# h_bridge.net
KiCad netlist of a schematic drawn in Altium Designer
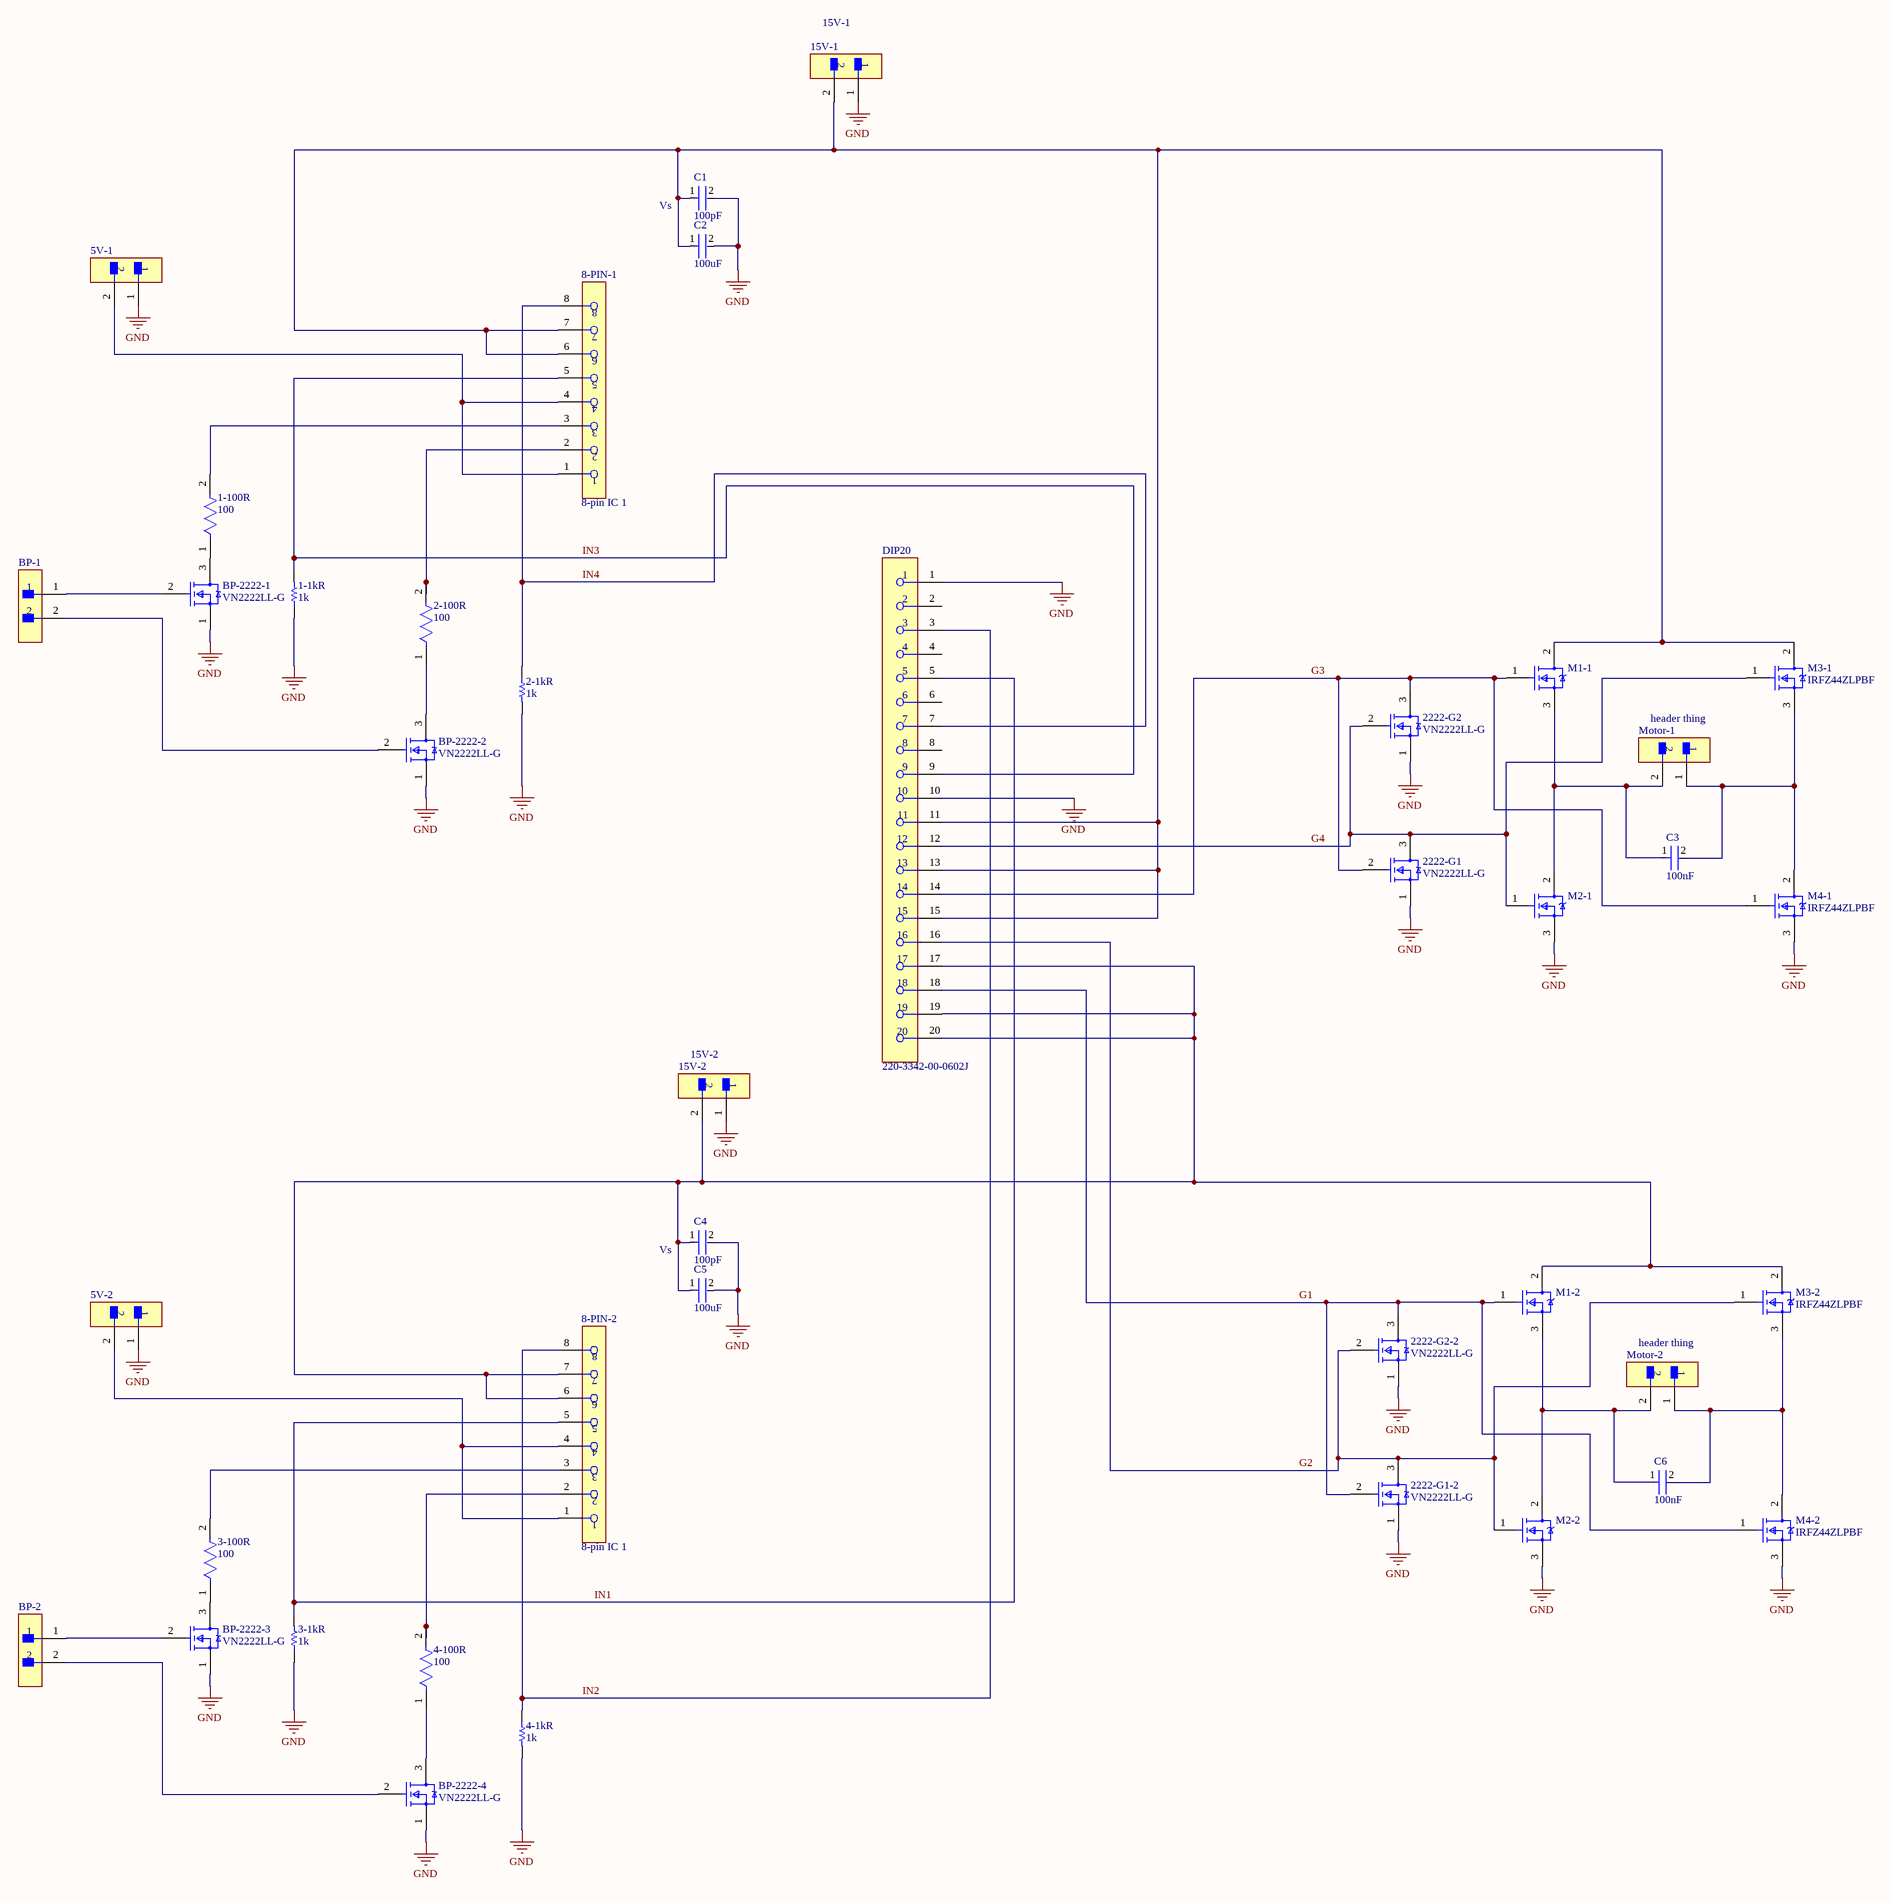
[diagram p0: h bridge.SchDoc]

(export (version "E")
  (design (tool "Eeschema 10.0.6"))
  (components
    (comp (ref "1-1kR")
      (value "1k")
      (footprint "RESC3116X65X40ML10T20")
      (description "Chip Resistor, 1 KOhm, +/- 1%, 0.25 W, -55 to 155 degC, 1206 (3216 Metric), RoHS, Tape and Reel")
      (fields (field (name "TOLERANCE") "1%") (field (name "MANUFACTURER") "Yageo"))
      (libsource (lib "Altium Content Vault") (part "RES-2"))
    )
    (comp (ref "1-100R")
      (value "100")
      (footprint "FP-CRCW1206-e3-MFG")
      (description "RES Thick Film, 100Ω, 1%, 0.25W, 100ppm/°C, 1206")
      (fields (field (name "TOLERANCE") "1%"))
      (libsource (lib "Altium Content Vault") (part "1029c3af85768c4190bb7ad29bc67b5"))
    )
    (comp (ref "2-1kR")
      (value "1k")
      (footprint "RESC3116X65X40ML10T20")
      (description "Chip Resistor, 1 KOhm, +/- 1%, 0.25 W, -55 to 155 degC, 1206 (3216 Metric), RoHS, Tape and Reel")
      (fields (field (name "TOLERANCE") "1%") (field (name "MANUFACTURER") "Yageo"))
      (libsource (lib "Altium Content Vault") (part "RES-2"))
    )
    (comp (ref "2-100R")
      (value "100")
      (footprint "FP-CRCW1206-e3-MFG")
      (description "RES Thick Film, 100Ω, 1%, 0.25W, 100ppm/°C, 1206")
      (fields (field (name "TOLERANCE") "1%"))
      (libsource (lib "Altium Content Vault") (part "1029c3af85768c4190bb7ad29bc67b5"))
    )
    (comp (ref "3-1kR")
      (value "1k")
      (footprint "RESC3116X65X40ML10T20")
      (description "Chip Resistor, 1 KOhm, +/- 1%, 0.25 W, -55 to 155 degC, 1206 (3216 Metric), RoHS, Tape and Reel")
      (fields (field (name "TOLERANCE") "1%") (field (name "MANUFACTURER") "Yageo"))
      (libsource (lib "Altium Content Vault") (part "RES-2"))
    )
    (comp (ref "3-100R")
      (value "100")
      (footprint "FP-CRCW1206-e3-MFG")
      (description "RES Thick Film, 100Ω, 1%, 0.25W, 100ppm/°C, 1206")
      (fields (field (name "TOLERANCE") "1%"))
      (libsource (lib "Altium Content Vault") (part "1029c3af85768c4190bb7ad29bc67b5"))
    )
    (comp (ref "4-1kR")
      (value "1k")
      (footprint "RESC3116X65X40ML10T20")
      (description "Chip Resistor, 1 KOhm, +/- 1%, 0.25 W, -55 to 155 degC, 1206 (3216 Metric), RoHS, Tape and Reel")
      (fields (field (name "TOLERANCE") "1%") (field (name "MANUFACTURER") "Yageo"))
      (libsource (lib "Altium Content Vault") (part "RES-2"))
    )
    (comp (ref "4-100R")
      (value "100")
      (footprint "FP-CRCW1206-e3-MFG")
      (description "RES Thick Film, 100Ω, 1%, 0.25W, 100ppm/°C, 1206")
      (fields (field (name "TOLERANCE") "1%"))
      (libsource (lib "Altium Content Vault") (part "1029c3af85768c4190bb7ad29bc67b5"))
    )
    (comp (ref "5V-1")
      (value "~")
      (footprint "FP-B2B-EH-A_LF_SN-MFG")
      (description "CONN HEADER VERT 2POS 2.5MM")
      (libsource (lib "") (part "3bc925449376181038e59eaffc5286c_1"))
    )
    (comp (ref "5V-2")
      (value "~")
      (footprint "FP-B2B-EH-A_LF_SN-MFG")
      (description "CONN HEADER VERT 2POS 2.5MM")
      (libsource (lib "") (part "3bc925449376181038e59eaffc5286c_1"))
    )
    (comp (ref "8-PIN-1")
      (value "8-pin IC 1")
      (footprint "FP-1-2199298-2-MFG")
      (description "CONN IC DIP SOCKET 8POS TIN")
      (libsource (lib "Altium Content Vault") (part "b0a0b555dd3abf3683e7c330df25cc4"))
    )
    (comp (ref "8-PIN-2")
      (value "8-pin IC 1")
      (footprint "FP-1-2199298-2-MFG")
      (description "CONN IC DIP SOCKET 8POS TIN")
      (libsource (lib "Altium Content Vault") (part "b0a0b555dd3abf3683e7c330df25cc4"))
    )
    (comp (ref "15V-1")
      (value "15V-1")
      (footprint "FP-B2B-EH-A_LF_SN-MFG")
      (description "CONN HEADER VERT 2POS 2.5MM")
      (libsource (lib "") (part "3bc925449376181038e59eaffc5286c_1"))
    )
    (comp (ref "15V-2")
      (value "15V-2")
      (footprint "FP-B2B-EH-A_LF_SN-MFG")
      (description "CONN HEADER VERT 2POS 2.5MM")
      (libsource (lib "") (part "3bc925449376181038e59eaffc5286c_1"))
    )
    (comp (ref "2222-G1")
      (value "VN2222LL-G")
      (footprint "FP-VN2222LL-G-MFG")
      (description "MOSFET N-CH 60V 0.23A TO92-3")
      (libsource (lib "Altium Content Vault") (part "4ab27c3d3892bfd5e8942bbbfba2a96"))
    )
    (comp (ref "2222-G1-2")
      (value "VN2222LL-G")
      (footprint "FP-VN2222LL-G-MFG")
      (description "MOSFET N-CH 60V 0.23A TO92-3")
      (libsource (lib "Altium Content Vault") (part "4ab27c3d3892bfd5e8942bbbfba2a96"))
    )
    (comp (ref "2222-G2")
      (value "VN2222LL-G")
      (footprint "FP-VN2222LL-G-MFG")
      (description "MOSFET N-CH 60V 0.23A TO92-3")
      (libsource (lib "Altium Content Vault") (part "4ab27c3d3892bfd5e8942bbbfba2a96"))
    )
    (comp (ref "2222-G2-2")
      (value "VN2222LL-G")
      (footprint "FP-VN2222LL-G-MFG")
      (description "MOSFET N-CH 60V 0.23A TO92-3")
      (libsource (lib "Altium Content Vault") (part "4ab27c3d3892bfd5e8942bbbfba2a96"))
    )
    (comp (ref "BP-1")
      (value "~")
      (footprint "FP-B2B-EH-A_LF_SN-MFG")
      (description "CONN HEADER VERT 2POS 2.5MM")
      (libsource (lib "Altium Content Vault") (part "3bc925449376181038e59eaffc5286c"))
    )
    (comp (ref "BP-2")
      (value "~")
      (footprint "FP-B2B-EH-A_LF_SN-MFG")
      (description "CONN HEADER VERT 2POS 2.5MM")
      (libsource (lib "Altium Content Vault") (part "3bc925449376181038e59eaffc5286c"))
    )
    (comp (ref "BP-2222-1")
      (value "VN2222LL-G")
      (footprint "FP-VN2222LL-G-MFG")
      (description "MOSFET N-CH 60V 0.23A TO92-3")
      (libsource (lib "Altium Content Vault") (part "4ab27c3d3892bfd5e8942bbbfba2a96"))
    )
    (comp (ref "BP-2222-2")
      (value "VN2222LL-G")
      (footprint "FP-VN2222LL-G-MFG")
      (description "MOSFET N-CH 60V 0.23A TO92-3")
      (libsource (lib "Altium Content Vault") (part "4ab27c3d3892bfd5e8942bbbfba2a96"))
    )
    (comp (ref "BP-2222-3")
      (value "VN2222LL-G")
      (footprint "FP-VN2222LL-G-MFG")
      (description "MOSFET N-CH 60V 0.23A TO92-3")
      (libsource (lib "Altium Content Vault") (part "4ab27c3d3892bfd5e8942bbbfba2a96"))
    )
    (comp (ref "BP-2222-4")
      (value "VN2222LL-G")
      (footprint "FP-VN2222LL-G-MFG")
      (description "MOSFET N-CH 60V 0.23A TO92-3")
      (libsource (lib "Altium Content Vault") (part "4ab27c3d3892bfd5e8942bbbfba2a96"))
    )
    (comp (ref "C1")
      (value "100pF")
      (footprint "FP-1206-L_3_2_0_2-W_1_6_0-MFG")
      (description "General Purpose Ceramic Capacitor, 1206, 100pF, 5%, NP0, 30ppm/°C, 100V")
      (fields (field (name "VOLTAGE") "63V") (field (name "TOLERANCE") "5%"))
      (libsource (lib "Altium Content Vault") (part "02cd4be3c70576c341d710602a673aa"))
    )
    (comp (ref "C2")
      (value "100uF")
      (footprint "FP-C3216-160-0_3-IPC_C")
      (description "Multilayer Ceramic Capacitors 100uF ±20% 10V X5R SMD 1206")
      (fields (field (name "VOLTAGE") "10V") (field (name "TOLERANCE") "20%"))
      (libsource (lib "Altium Content Vault") (part "02cd4be3c70576c341d710602a673aa"))
    )
    (comp (ref "C3")
      (value "100nF")
      (footprint "FP-1206-L_3_2_0_2-W_1_6_0-IPC_C")
      (description "General Purpose Ceramic Capacitor, 1206, 100nF, 5%, X7R, 15%, 100V")
      (fields (field (name "TOLERANCE") "5%") (field (name "VOLTAGE") "100V"))
      (libsource (lib "Altium Content Vault") (part "b4654b650e69147ec39a6b967a45e02"))
    )
    (comp (ref "C4")
      (value "100pF")
      (footprint "FP-1206-L_3_2_0_2-W_1_6_0-MFG")
      (description "General Purpose Ceramic Capacitor, 1206, 100pF, 5%, NP0, 30ppm/°C, 100V")
      (fields (field (name "VOLTAGE") "63V") (field (name "TOLERANCE") "5%"))
      (libsource (lib "Altium Content Vault") (part "02cd4be3c70576c341d710602a673aa"))
    )
    (comp (ref "C5")
      (value "100uF")
      (footprint "FP-C3216-160-0_3-IPC_C")
      (description "Multilayer Ceramic Capacitors 100uF ±20% 10V X5R SMD 1206")
      (fields (field (name "VOLTAGE") "10V") (field (name "TOLERANCE") "20%"))
      (libsource (lib "Altium Content Vault") (part "02cd4be3c70576c341d710602a673aa"))
    )
    (comp (ref "C6")
      (value "100nF")
      (footprint "FP-1206-L_3_2_0_2-W_1_6_0-IPC_C")
      (description "General Purpose Ceramic Capacitor, 1206, 100nF, 5%, X7R, 15%, 100V")
      (fields (field (name "TOLERANCE") "5%") (field (name "VOLTAGE") "100V"))
      (libsource (lib "Altium Content Vault") (part "b4654b650e69147ec39a6b967a45e02"))
    )
    (comp (ref "DIP20")
      (value "220-3342-00-0602J")
      (footprint "FP-220-3342-00-0602J-0")
      (description "20 (2 x 10) Pos DIP, ZIF (ZIP), 0.3\" (7.62mm) Row Spacing Socket Gold Connector")
      (fields (field (name "MANUFACTURER") "3M"))
      (libsource (lib "Altium Content Vault") (part "dba14e038e6f7492952b7f1e871f183"))
    )
    (comp (ref "M1-1")
      (value "IRFZ44ZLPBF")
      (footprint "FP-PG-TO262-3-MFG")
      (description "MOSFET N-CH 55V 51A TO262")
      (libsource (lib "Altium Content Vault") (part "b09f7f152735e370c1ea22a33fa83d6"))
    )
    (comp (ref "M1-2")
      (value "IRFZ44ZLPBF")
      (footprint "FP-PG-TO262-3-MFG")
      (description "MOSFET N-CH 55V 51A TO262")
      (libsource (lib "Altium Content Vault") (part "b09f7f152735e370c1ea22a33fa83d6"))
    )
    (comp (ref "M2-1")
      (value "IRFZ44ZLPBF")
      (footprint "FP-PG-TO262-3-MFG")
      (description "MOSFET N-CH 55V 51A TO262")
      (libsource (lib "Altium Content Vault") (part "b09f7f152735e370c1ea22a33fa83d6"))
    )
    (comp (ref "M2-2")
      (value "IRFZ44ZLPBF")
      (footprint "FP-PG-TO262-3-MFG")
      (description "MOSFET N-CH 55V 51A TO262")
      (libsource (lib "Altium Content Vault") (part "b09f7f152735e370c1ea22a33fa83d6"))
    )
    (comp (ref "M3-1")
      (value "IRFZ44ZLPBF")
      (footprint "FP-PG-TO262-3-MFG")
      (description "MOSFET N-CH 55V 51A TO262")
      (libsource (lib "Altium Content Vault") (part "b09f7f152735e370c1ea22a33fa83d6"))
    )
    (comp (ref "M3-2")
      (value "IRFZ44ZLPBF")
      (footprint "FP-PG-TO262-3-MFG")
      (description "MOSFET N-CH 55V 51A TO262")
      (libsource (lib "Altium Content Vault") (part "b09f7f152735e370c1ea22a33fa83d6"))
    )
    (comp (ref "M4-1")
      (value "IRFZ44ZLPBF")
      (footprint "FP-PG-TO262-3-MFG")
      (description "MOSFET N-CH 55V 51A TO262")
      (libsource (lib "Altium Content Vault") (part "b09f7f152735e370c1ea22a33fa83d6"))
    )
    (comp (ref "M4-2")
      (value "IRFZ44ZLPBF")
      (footprint "FP-PG-TO262-3-MFG")
      (description "MOSFET N-CH 55V 51A TO262")
      (libsource (lib "Altium Content Vault") (part "b09f7f152735e370c1ea22a33fa83d6"))
    )
    (comp (ref "Motor-1")
      (value "header thing")
      (footprint "FP-B2B-EH-A_LF_SN-MFG")
      (description "CONN HEADER VERT 2POS 2.5MM")
      (libsource (lib "") (part "3bc925449376181038e59eaffc5286c_1"))
    )
    (comp (ref "Motor-2")
      (value "header thing")
      (footprint "FP-B2B-EH-A_LF_SN-MFG")
      (description "CONN HEADER VERT 2POS 2.5MM")
      (libsource (lib "") (part "3bc925449376181038e59eaffc5286c_1"))
    )
  )
  (nets
    (net (code "1") (name "/G1") (class "Default")
      (node (ref "2222-G1-2") (pin "2") (pinfunction "GATE_2") (pintype "passive"))
      (node (ref "2222-G2-2") (pin "3") (pinfunction "DRAIN_3") (pintype "passive"))
      (node (ref "DIP20") (pin "18") (pinfunction "18_18") (pintype "passive"))
      (node (ref "M1-2") (pin "1") (pinfunction "G_1") (pintype "passive"))
      (node (ref "M4-2") (pin "1") (pinfunction "G_1") (pintype "passive"))
    )
    (net (code "2") (name "/G2") (class "Default")
      (node (ref "2222-G1-2") (pin "3") (pinfunction "DRAIN_3") (pintype "passive"))
      (node (ref "2222-G2-2") (pin "2") (pinfunction "GATE_2") (pintype "passive"))
      (node (ref "DIP20") (pin "16") (pinfunction "16_16") (pintype "passive"))
      (node (ref "M2-2") (pin "1") (pinfunction "G_1") (pintype "passive"))
      (node (ref "M3-2") (pin "1") (pinfunction "G_1") (pintype "passive"))
    )
    (net (code "3") (name "/G3") (class "Default")
      (node (ref "2222-G1") (pin "2") (pinfunction "GATE_2") (pintype "passive"))
      (node (ref "2222-G2") (pin "3") (pinfunction "DRAIN_3") (pintype "passive"))
      (node (ref "DIP20") (pin "14") (pinfunction "14_14") (pintype "passive"))
      (node (ref "M1-1") (pin "1") (pinfunction "G_1") (pintype "passive"))
      (node (ref "M4-1") (pin "1") (pinfunction "G_1") (pintype "passive"))
    )
    (net (code "4") (name "/G4") (class "Default")
      (node (ref "2222-G1") (pin "3") (pinfunction "DRAIN_3") (pintype "passive"))
      (node (ref "2222-G2") (pin "2") (pinfunction "GATE_2") (pintype "passive"))
      (node (ref "DIP20") (pin "12") (pinfunction "12_12") (pintype "passive"))
      (node (ref "M2-1") (pin "1") (pinfunction "G_1") (pintype "passive"))
      (node (ref "M3-1") (pin "1") (pinfunction "G_1") (pintype "passive"))
    )
    (net (code "5") (name "/IN1") (class "Default")
      (node (ref "3-1kR") (pin "2") (pinfunction "2_2") (pintype "passive"))
      (node (ref "8-PIN-2") (pin "5") (pinfunction "5_5") (pintype "passive"))
      (node (ref "DIP20") (pin "5") (pinfunction "5_5") (pintype "passive"))
    )
    (net (code "6") (name "/IN2") (class "Default")
      (node (ref "4-1kR") (pin "1") (pinfunction "1_1") (pintype "passive"))
      (node (ref "8-PIN-2") (pin "8") (pinfunction "8_8") (pintype "passive"))
      (node (ref "DIP20") (pin "3") (pinfunction "3_3") (pintype "passive"))
    )
    (net (code "7") (name "/IN3") (class "Default")
      (node (ref "1-1kR") (pin "2") (pinfunction "2_2") (pintype "passive"))
      (node (ref "8-PIN-1") (pin "5") (pinfunction "5_5") (pintype "passive"))
      (node (ref "DIP20") (pin "9") (pinfunction "9_9") (pintype "passive"))
    )
    (net (code "8") (name "/IN4") (class "Default")
      (node (ref "2-1kR") (pin "1") (pinfunction "1_1") (pintype "passive"))
      (node (ref "8-PIN-1") (pin "8") (pinfunction "8_8") (pintype "passive"))
      (node (ref "DIP20") (pin "7") (pinfunction "7_7") (pintype "passive"))
    )
    (net (code "9") (name "GND") (class "Default")
      (node (ref "1-1kR") (pin "1") (pinfunction "1_1") (pintype "passive"))
      (node (ref "15V-1") (pin "1") (pinfunction "1_1") (pintype "passive"))
      (node (ref "15V-2") (pin "1") (pinfunction "1_1") (pintype "passive"))
      (node (ref "2-1kR") (pin "2") (pinfunction "2_2") (pintype "passive"))
      (node (ref "2222-G1") (pin "1") (pinfunction "SOURCE_1") (pintype "passive"))
      (node (ref "2222-G1-2") (pin "1") (pinfunction "SOURCE_1") (pintype "passive"))
      (node (ref "2222-G2") (pin "1") (pinfunction "SOURCE_1") (pintype "passive"))
      (node (ref "2222-G2-2") (pin "1") (pinfunction "SOURCE_1") (pintype "passive"))
      (node (ref "3-1kR") (pin "1") (pinfunction "1_1") (pintype "passive"))
      (node (ref "4-1kR") (pin "2") (pinfunction "2_2") (pintype "passive"))
      (node (ref "5V-1") (pin "1") (pinfunction "1_1") (pintype "passive"))
      (node (ref "5V-2") (pin "1") (pinfunction "1_1") (pintype "passive"))
      (node (ref "BP-2222-1") (pin "1") (pinfunction "SOURCE_1") (pintype "passive"))
      (node (ref "BP-2222-2") (pin "1") (pinfunction "SOURCE_1") (pintype "passive"))
      (node (ref "BP-2222-3") (pin "1") (pinfunction "SOURCE_1") (pintype "passive"))
      (node (ref "BP-2222-4") (pin "1") (pinfunction "SOURCE_1") (pintype "passive"))
      (node (ref "C1") (pin "2") (pinfunction "2_2") (pintype "passive"))
      (node (ref "C2") (pin "2") (pinfunction "2_2") (pintype "passive"))
      (node (ref "C4") (pin "2") (pinfunction "2_2") (pintype "passive"))
      (node (ref "C5") (pin "2") (pinfunction "2_2") (pintype "passive"))
      (node (ref "DIP20") (pin "1") (pinfunction "1_1") (pintype "passive"))
      (node (ref "DIP20") (pin "10") (pinfunction "10_10") (pintype "passive"))
      (node (ref "M2-1") (pin "3") (pinfunction "S_3") (pintype "passive"))
      (node (ref "M2-2") (pin "3") (pinfunction "S_3") (pintype "passive"))
      (node (ref "M4-1") (pin "3") (pinfunction "S_3") (pintype "passive"))
      (node (ref "M4-2") (pin "3") (pinfunction "S_3") (pintype "passive"))
    )
    (net (code "10") (name "Net-(1-100R-Pad2)") (class "Default")
      (node (ref "1-100R") (pin "2") (pinfunction "2_2") (pintype "passive"))
      (node (ref "8-PIN-1") (pin "3") (pinfunction "3_3") (pintype "passive"))
    )
    (net (code "11") (name "Net-(2-100R-Pad2)") (class "Default")
      (node (ref "2-100R") (pin "2") (pinfunction "2_2") (pintype "passive"))
      (node (ref "8-PIN-1") (pin "2") (pinfunction "2_2") (pintype "passive"))
    )
    (net (code "12") (name "Net-(3-100R-Pad2)") (class "Default")
      (node (ref "3-100R") (pin "2") (pinfunction "2_2") (pintype "passive"))
      (node (ref "8-PIN-2") (pin "3") (pinfunction "3_3") (pintype "passive"))
    )
    (net (code "13") (name "Net-(4-100R-Pad2)") (class "Default")
      (node (ref "4-100R") (pin "2") (pinfunction "2_2") (pintype "passive"))
      (node (ref "8-PIN-2") (pin "2") (pinfunction "2_2") (pintype "passive"))
    )
    (net (code "14") (name "Net-(5V-1-Pad2)") (class "Default")
      (node (ref "5V-1") (pin "2") (pinfunction "2_2") (pintype "passive"))
      (node (ref "8-PIN-1") (pin "1") (pinfunction "1_1") (pintype "passive"))
      (node (ref "8-PIN-1") (pin "4") (pinfunction "4_4") (pintype "passive"))
    )
    (net (code "15") (name "Net-(5V-2-Pad2)") (class "Default")
      (node (ref "5V-2") (pin "2") (pinfunction "2_2") (pintype "passive"))
      (node (ref "8-PIN-2") (pin "1") (pinfunction "1_1") (pintype "passive"))
      (node (ref "8-PIN-2") (pin "4") (pinfunction "4_4") (pintype "passive"))
    )
    (net (code "16") (name "Net-(BP-2222-1-DRAIN)") (class "Default")
      (node (ref "1-100R") (pin "1") (pinfunction "1_1") (pintype "passive"))
      (node (ref "BP-2222-1") (pin "3") (pinfunction "DRAIN_3") (pintype "passive"))
    )
    (net (code "17") (name "Net-(BP-2222-1-GATE)") (class "Default")
      (node (ref "BP-1") (pin "1") (pinfunction "1_1") (pintype "passive"))
      (node (ref "BP-2222-1") (pin "2") (pinfunction "GATE_2") (pintype "passive"))
    )
    (net (code "18") (name "Net-(BP-2222-2-DRAIN)") (class "Default")
      (node (ref "2-100R") (pin "1") (pinfunction "1_1") (pintype "passive"))
      (node (ref "BP-2222-2") (pin "3") (pinfunction "DRAIN_3") (pintype "passive"))
    )
    (net (code "19") (name "Net-(BP-2222-2-GATE)") (class "Default")
      (node (ref "BP-1") (pin "2") (pinfunction "2_2") (pintype "passive"))
      (node (ref "BP-2222-2") (pin "2") (pinfunction "GATE_2") (pintype "passive"))
    )
    (net (code "20") (name "Net-(BP-2222-3-DRAIN)") (class "Default")
      (node (ref "3-100R") (pin "1") (pinfunction "1_1") (pintype "passive"))
      (node (ref "BP-2222-3") (pin "3") (pinfunction "DRAIN_3") (pintype "passive"))
    )
    (net (code "21") (name "Net-(BP-2222-3-GATE)") (class "Default")
      (node (ref "BP-2") (pin "1") (pinfunction "1_1") (pintype "passive"))
      (node (ref "BP-2222-3") (pin "2") (pinfunction "GATE_2") (pintype "passive"))
    )
    (net (code "22") (name "Net-(BP-2222-4-DRAIN)") (class "Default")
      (node (ref "4-100R") (pin "1") (pinfunction "1_1") (pintype "passive"))
      (node (ref "BP-2222-4") (pin "3") (pinfunction "DRAIN_3") (pintype "passive"))
    )
    (net (code "23") (name "Net-(BP-2222-4-GATE)") (class "Default")
      (node (ref "BP-2") (pin "2") (pinfunction "2_2") (pintype "passive"))
      (node (ref "BP-2222-4") (pin "2") (pinfunction "GATE_2") (pintype "passive"))
    )
    (net (code "24") (name "Net-(M1-1-D)") (class "Default")
      (node (ref "15V-1") (pin "2") (pinfunction "2_2") (pintype "passive"))
      (node (ref "8-PIN-1") (pin "6") (pinfunction "6_6") (pintype "passive"))
      (node (ref "8-PIN-1") (pin "7") (pinfunction "7_7") (pintype "passive"))
      (node (ref "C1") (pin "1") (pinfunction "1_1") (pintype "passive"))
      (node (ref "C2") (pin "1") (pinfunction "1_1") (pintype "passive"))
      (node (ref "DIP20") (pin "11") (pinfunction "11_11") (pintype "passive"))
      (node (ref "DIP20") (pin "13") (pinfunction "13_13") (pintype "passive"))
      (node (ref "DIP20") (pin "15") (pinfunction "15_15") (pintype "passive"))
      (node (ref "M1-1") (pin "2") (pinfunction "D_2") (pintype "passive"))
      (node (ref "M3-1") (pin "2") (pinfunction "D_2") (pintype "passive"))
    )
    (net (code "25") (name "Net-(M1-1-S)") (class "Default")
      (node (ref "C3") (pin "1") (pinfunction "1_1") (pintype "passive"))
      (node (ref "M1-1") (pin "3") (pinfunction "S_3") (pintype "passive"))
      (node (ref "M2-1") (pin "2") (pinfunction "D_2") (pintype "passive"))
      (node (ref "Motor-1") (pin "2") (pinfunction "2_2") (pintype "passive"))
    )
    (net (code "26") (name "Net-(M1-2-D)") (class "Default")
      (node (ref "15V-2") (pin "2") (pinfunction "2_2") (pintype "passive"))
      (node (ref "8-PIN-2") (pin "6") (pinfunction "6_6") (pintype "passive"))
      (node (ref "8-PIN-2") (pin "7") (pinfunction "7_7") (pintype "passive"))
      (node (ref "C4") (pin "1") (pinfunction "1_1") (pintype "passive"))
      (node (ref "C5") (pin "1") (pinfunction "1_1") (pintype "passive"))
      (node (ref "DIP20") (pin "17") (pinfunction "17_17") (pintype "passive"))
      (node (ref "DIP20") (pin "19") (pinfunction "19_19") (pintype "passive"))
      (node (ref "DIP20") (pin "20") (pinfunction "20_20") (pintype "passive"))
      (node (ref "M1-2") (pin "2") (pinfunction "D_2") (pintype "passive"))
      (node (ref "M3-2") (pin "2") (pinfunction "D_2") (pintype "passive"))
    )
    (net (code "27") (name "Net-(M1-2-S)") (class "Default")
      (node (ref "C6") (pin "1") (pinfunction "1_1") (pintype "passive"))
      (node (ref "M1-2") (pin "3") (pinfunction "S_3") (pintype "passive"))
      (node (ref "M2-2") (pin "2") (pinfunction "D_2") (pintype "passive"))
      (node (ref "Motor-2") (pin "2") (pinfunction "2_2") (pintype "passive"))
    )
    (net (code "28") (name "Net-(M3-1-S)") (class "Default")
      (node (ref "C3") (pin "2") (pinfunction "2_2") (pintype "passive"))
      (node (ref "M3-1") (pin "3") (pinfunction "S_3") (pintype "passive"))
      (node (ref "M4-1") (pin "2") (pinfunction "D_2") (pintype "passive"))
      (node (ref "Motor-1") (pin "1") (pinfunction "1_1") (pintype "passive"))
    )
    (net (code "29") (name "Net-(M3-2-S)") (class "Default")
      (node (ref "C6") (pin "2") (pinfunction "2_2") (pintype "passive"))
      (node (ref "M3-2") (pin "3") (pinfunction "S_3") (pintype "passive"))
      (node (ref "M4-2") (pin "2") (pinfunction "D_2") (pintype "passive"))
      (node (ref "Motor-2") (pin "1") (pinfunction "1_1") (pintype "passive"))
    )
    (net (code "30") (name "unconnected-(DIP20-Pad2)") (class "Default")
      (node (ref "DIP20") (pin "2") (pinfunction "2_2") (pintype "passive"))
    )
    (net (code "31") (name "unconnected-(DIP20-Pad4)") (class "Default")
      (node (ref "DIP20") (pin "4") (pinfunction "4_4") (pintype "passive"))
    )
    (net (code "32") (name "unconnected-(DIP20-Pad6)") (class "Default")
      (node (ref "DIP20") (pin "6") (pinfunction "6_6") (pintype "passive"))
    )
    (net (code "33") (name "unconnected-(DIP20-Pad8)") (class "Default")
      (node (ref "DIP20") (pin "8") (pinfunction "8_8") (pintype "passive"))
    )
  )
)
